# Proto4_main_board.net
KiCad netlist of a schematic drawn in EAGLE
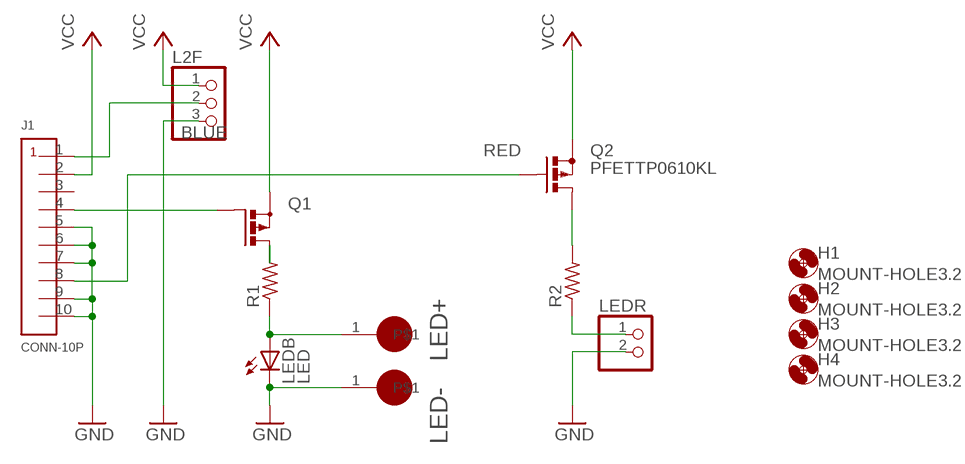
[diagram p0: schematic, sheet 1]

(export (version "E")
  (design (tool "Eeschema 10.0.6"))
  (components
    (comp (ref "H1")
      (value "MOUNT-HOLE3.2")
      (footprint "eagle-import:3,2")
      (libsource (lib "eagle-import") (part "MOUNT-HOLE3.2"))
    )
    (comp (ref "H2")
      (value "MOUNT-HOLE3.2")
      (footprint "eagle-import:3,2")
      (libsource (lib "eagle-import") (part "MOUNT-HOLE3.2"))
    )
    (comp (ref "H3")
      (value "MOUNT-HOLE3.2")
      (footprint "eagle-import:3,2")
      (libsource (lib "eagle-import") (part "MOUNT-HOLE3.2"))
    )
    (comp (ref "H4")
      (value "MOUNT-HOLE3.2")
      (footprint "eagle-import:3,2")
      (libsource (lib "eagle-import") (part "MOUNT-HOLE3.2"))
    )
    (comp (ref "J1")
      (value "CONN-10P")
      (footprint "eagle-import:MICROMATCH-10P-SMD")
      (libsource (lib "eagle-import") (part "CONN-10P"))
    )
    (comp (ref "L2F")
      (value "PINHD-1X3/90")
      (footprint "eagle-import:1X03_90")
      (libsource (lib "eagle-import") (part "PINHD-1X3/90"))
    )
    (comp (ref "LED+")
      (value "TP")
      (footprint "eagle-import:LARGE_PAD")
      (libsource (lib "eagle-import") (part "TP"))
    )
    (comp (ref "LED-")
      (value "TP")
      (footprint "eagle-import:LARGE_PAD")
      (libsource (lib "eagle-import") (part "TP"))
    )
    (comp (ref "LEDB")
      (value "LED")
      (footprint "eagle-import:CREE-XP-E2")
      (libsource (lib "eagle-import") (part "LED"))
    )
    (comp (ref "LEDR")
      (value "PINHD-1X2/90")
      (footprint "eagle-import:1X02_90")
      (libsource (lib "eagle-import") (part "PINHD-1X2/90"))
    )
    (comp (ref "Q1")
      (value "PMOSFET_PTO220BH")
      (footprint "eagle-import:TO220BH")
      (libsource (lib "eagle-import") (part "PMOSFET_PTO220BH"))
    )
    (comp (ref "Q2")
      (value "PFETTP0610KL")
      (footprint "eagle-import:TO92-OVAL")
      (libsource (lib "eagle-import") (part "PFETTP0610KL"))
    )
    (comp (ref "R1")
      (value "R-US_0414/15")
      (footprint "eagle-import:0414_15")
      (libsource (lib "eagle-import") (part "R-US_0414/15"))
    )
    (comp (ref "R2")
      (value "R-US_0309/12")
      (footprint "eagle-import:0309_12")
      (libsource (lib "eagle-import") (part "R-US_0309/12"))
    )
  )
  (nets
    (net (code "1") (name "/BLUE") (class "Default")
      (node (ref "J1") (pin "4") (pinfunction "4_4") (pintype "bidirectional"))
      (node (ref "Q1") (pin "G") (pinfunction "G_G") (pintype "passive"))
    )
    (net (code "2") (name "/RED") (class "Default")
      (node (ref "J1") (pin "8") (pinfunction "8_8") (pintype "bidirectional"))
      (node (ref "Q2") (pin "2") (pinfunction "G_2") (pintype "passive"))
    )
    (net (code "3") (name "GND") (class "Default")
      (node (ref "J1") (pin "10") (pinfunction "10_10") (pintype "bidirectional"))
      (node (ref "J1") (pin "5") (pinfunction "5_5") (pintype "bidirectional"))
      (node (ref "J1") (pin "6") (pinfunction "6_6") (pintype "bidirectional"))
      (node (ref "J1") (pin "7") (pinfunction "7_7") (pintype "bidirectional"))
      (node (ref "J1") (pin "9") (pinfunction "9_9") (pintype "bidirectional"))
      (node (ref "L2F") (pin "3") (pinfunction "3_3") (pintype "passive"))
      (node (ref "LED-") (pin "1") (pinfunction "P$1_1") (pintype "bidirectional"))
      (node (ref "LEDB") (pin "2") (pinfunction "C_2") (pintype "passive"))
      (node (ref "LEDR") (pin "2") (pinfunction "2_2") (pintype "passive"))
    )
    (net (code "4") (name "Net-(J1-Pad1)") (class "Default")
      (node (ref "J1") (pin "1") (pinfunction "1_1") (pintype "bidirectional"))
      (node (ref "L2F") (pin "2") (pinfunction "2_2") (pintype "passive"))
    )
    (net (code "5") (name "Net-(LED+-P$1)") (class "Default")
      (node (ref "LED+") (pin "1") (pinfunction "P$1_1") (pintype "bidirectional"))
      (node (ref "LEDB") (pin "1") (pinfunction "A_1") (pintype "passive"))
      (node (ref "R1") (pin "1") (pinfunction "1_1") (pintype "passive"))
    )
    (net (code "6") (name "Net-(LEDR-Pad1)") (class "Default")
      (node (ref "LEDR") (pin "1") (pinfunction "1_1") (pintype "passive"))
      (node (ref "R2") (pin "1") (pinfunction "1_1") (pintype "passive"))
    )
    (net (code "7") (name "Net-(Q1-PadD)") (class "Default")
      (node (ref "Q1") (pin "D") (pinfunction "D_D") (pintype "passive"))
      (node (ref "R1") (pin "2") (pinfunction "2_2") (pintype "passive"))
    )
    (net (code "8") (name "Net-(Q2-D)") (class "Default")
      (node (ref "Q2") (pin "3") (pinfunction "D_3") (pintype "passive"))
      (node (ref "R2") (pin "2") (pinfunction "2_2") (pintype "passive"))
    )
    (net (code "9") (name "VCC") (class "Default")
      (node (ref "J1") (pin "2") (pinfunction "2_2") (pintype "bidirectional"))
      (node (ref "L2F") (pin "1") (pinfunction "1_1") (pintype "passive"))
      (node (ref "Q1") (pin "S") (pinfunction "S_S") (pintype "passive"))
      (node (ref "Q2") (pin "1") (pinfunction "S_1") (pintype "passive"))
    )
    (net (code "10") (name "unconnected-(J1-Pad3)") (class "Default")
      (node (ref "J1") (pin "3") (pinfunction "3_3") (pintype "bidirectional"))
    )
  )
)
